# 12A-03.net
KiCad netlist of a schematic drawn in EAGLE
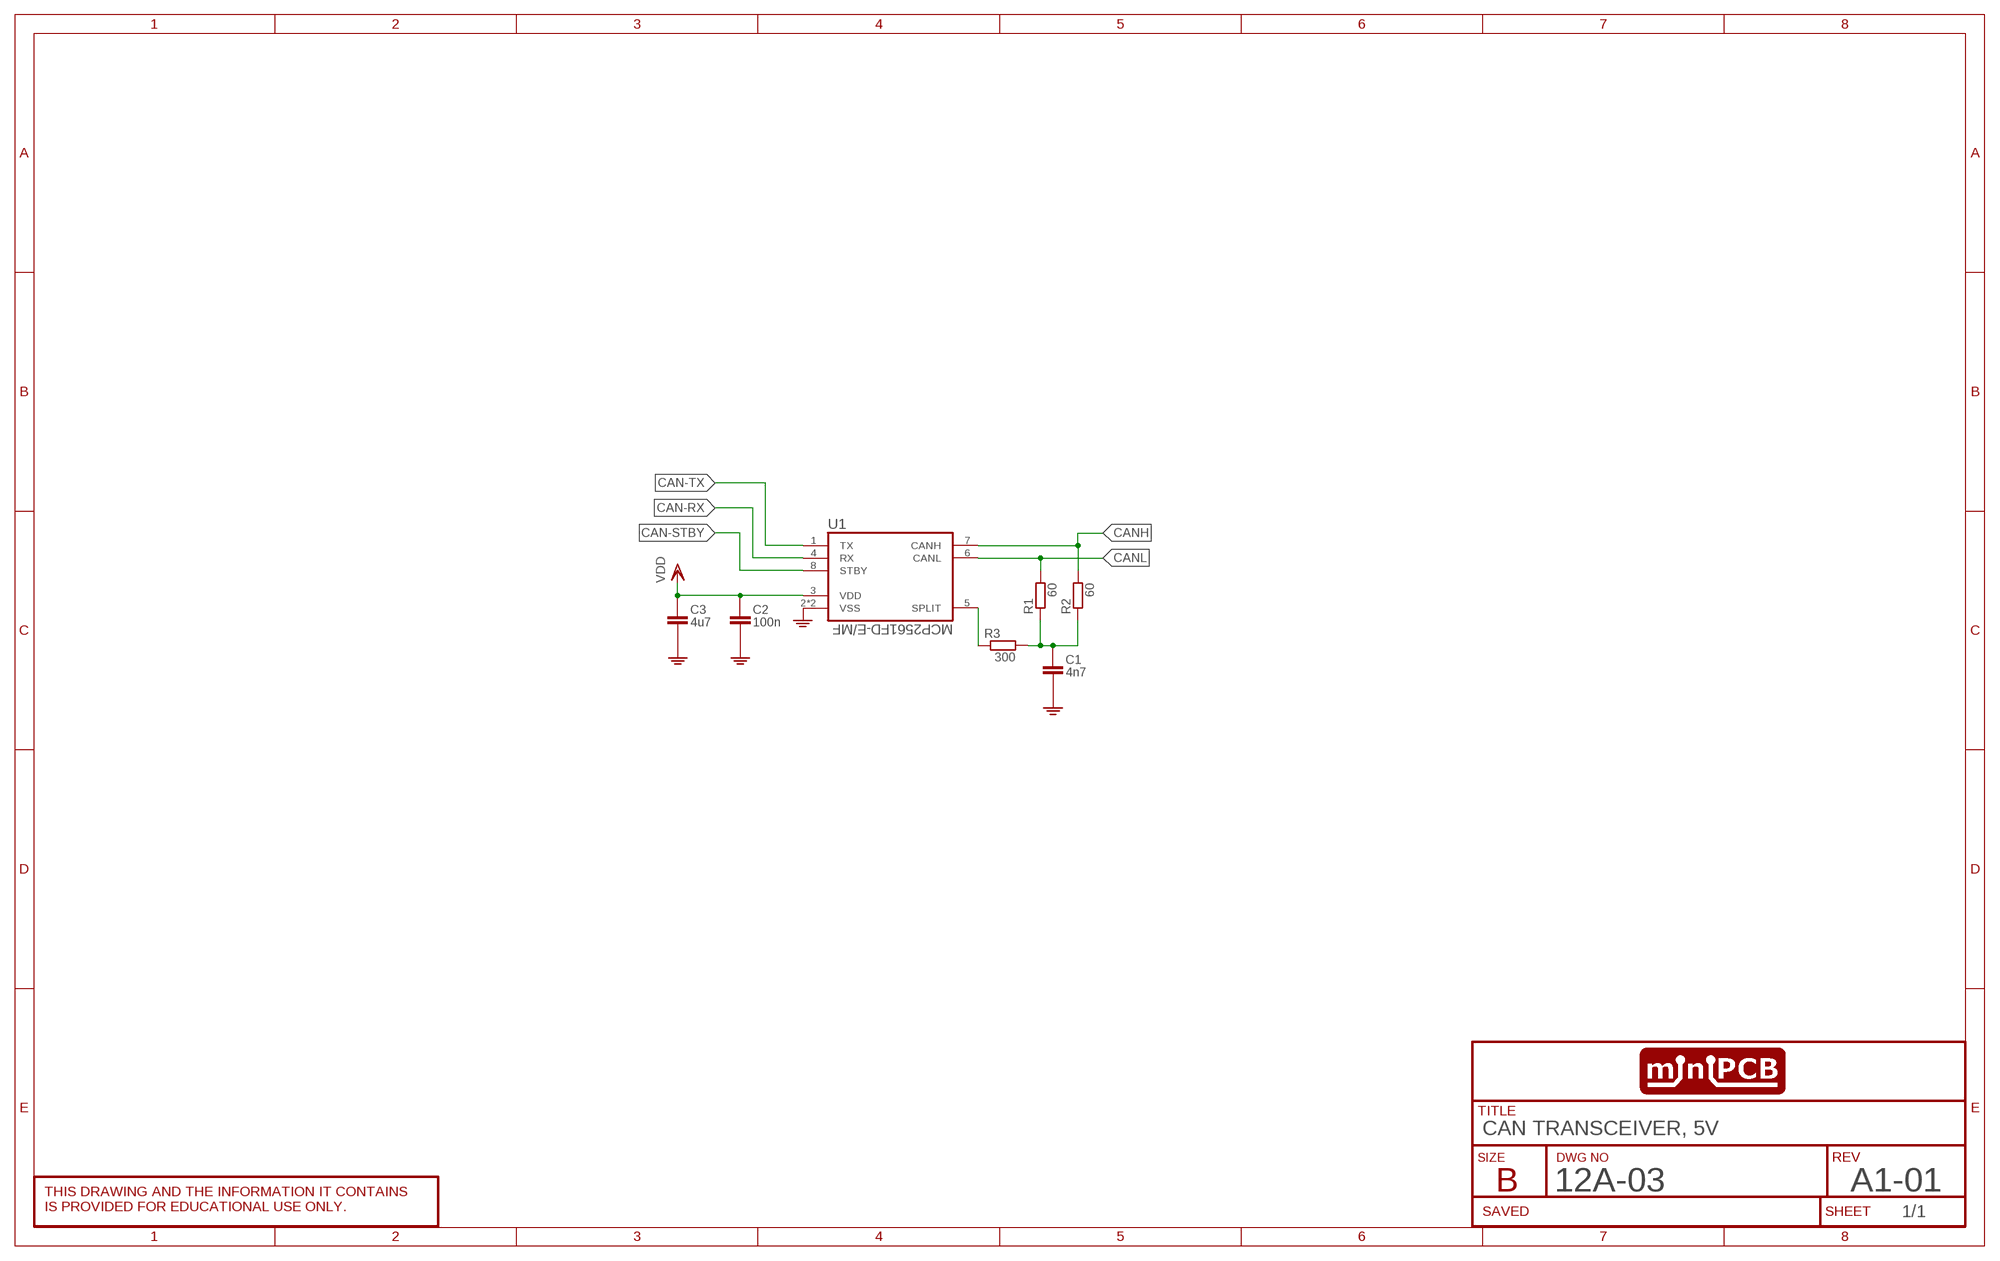
[diagram p0: schematic, sheet 1]

(export (version "E")
  (design (tool "Eeschema 10.0.6"))
  (components
    (comp (ref "C1")
      (value "4n7")
      (footprint "eagle-import:C0402")
      (libsource (lib "eagle-import") (part "CAPACITOR0402"))
    )
    (comp (ref "C2")
      (value "100n")
      (footprint "eagle-import:C0402")
      (libsource (lib "eagle-import") (part "CAPACITOR0402"))
    )
    (comp (ref "C3")
      (value "4u7")
      (footprint "eagle-import:C0402")
      (libsource (lib "eagle-import") (part "CAPACITOR0402"))
    )
    (comp (ref "R1")
      (value "60")
      (footprint "eagle-import:R0402")
      (libsource (lib "eagle-import") (part "RESISTOR0402"))
    )
    (comp (ref "R2")
      (value "60")
      (footprint "eagle-import:R0402")
      (libsource (lib "eagle-import") (part "RESISTOR0402"))
    )
    (comp (ref "R3")
      (value "300")
      (footprint "eagle-import:R0402")
      (libsource (lib "eagle-import") (part "RESISTOR0402"))
    )
    (comp (ref "U1")
      (value "MCP2561FD-E/MF")
      (footprint "eagle-import:SON65P300X300X100-9N")
      (libsource (lib "eagle-import") (part "MCP2561FD-E/MF"))
    )
  )
  (nets
    (net (code "1") (name "CAN-RX") (class "Default")
      (node (ref "U1") (pin "4") (pinfunction "RX_4") (pintype "input"))
    )
    (net (code "2") (name "CAN-STBY") (class "Default")
      (node (ref "U1") (pin "8") (pinfunction "STBY_8") (pintype "power_in"))
    )
    (net (code "3") (name "CAN-TX") (class "Default")
      (node (ref "U1") (pin "1") (pinfunction "TX_1") (pintype "bidirectional"))
    )
    (net (code "4") (name "CANH") (class "Default")
      (node (ref "R2") (pin "2") (pinfunction "2_2") (pintype "passive"))
      (node (ref "U1") (pin "7") (pinfunction "CANH_7") (pintype "bidirectional"))
    )
    (net (code "5") (name "CANL") (class "Default")
      (node (ref "R1") (pin "2") (pinfunction "2_2") (pintype "passive"))
      (node (ref "U1") (pin "6") (pinfunction "CANL_6") (pintype "input"))
    )
    (net (code "6") (name "GND") (class "Default")
      (node (ref "C1") (pin "2") (pinfunction "-_2") (pintype "passive"))
      (node (ref "C2") (pin "2") (pinfunction "-_2") (pintype "passive"))
      (node (ref "C3") (pin "2") (pinfunction "-_2") (pintype "passive"))
      (node (ref "U1") (pin "2") (pinfunction "VSS_2") (pintype "passive"))
      (node (ref "U1") (pin "9") (pinfunction "VSS_9") (pintype "passive"))
    )
    (net (code "7") (name "Net-(C1-+)") (class "Default")
      (node (ref "C1") (pin "1") (pinfunction "+_1") (pintype "passive"))
      (node (ref "R1") (pin "1") (pinfunction "1_1") (pintype "passive"))
      (node (ref "R2") (pin "1") (pinfunction "1_1") (pintype "passive"))
      (node (ref "R3") (pin "2") (pinfunction "2_2") (pintype "passive"))
    )
    (net (code "8") (name "Net-(U1-SPLIT)") (class "Default")
      (node (ref "R3") (pin "1") (pinfunction "1_1") (pintype "passive"))
      (node (ref "U1") (pin "5") (pinfunction "SPLIT_5") (pintype "passive"))
    )
    (net (code "9") (name "VDD") (class "Default")
      (node (ref "C2") (pin "1") (pinfunction "+_1") (pintype "passive"))
      (node (ref "C3") (pin "1") (pinfunction "+_1") (pintype "passive"))
      (node (ref "U1") (pin "3") (pinfunction "VDD_3") (pintype "power_in"))
    )
  )
)
